# SENSOR_PB.net
KiCad netlist of a schematic drawn in Altium Designer
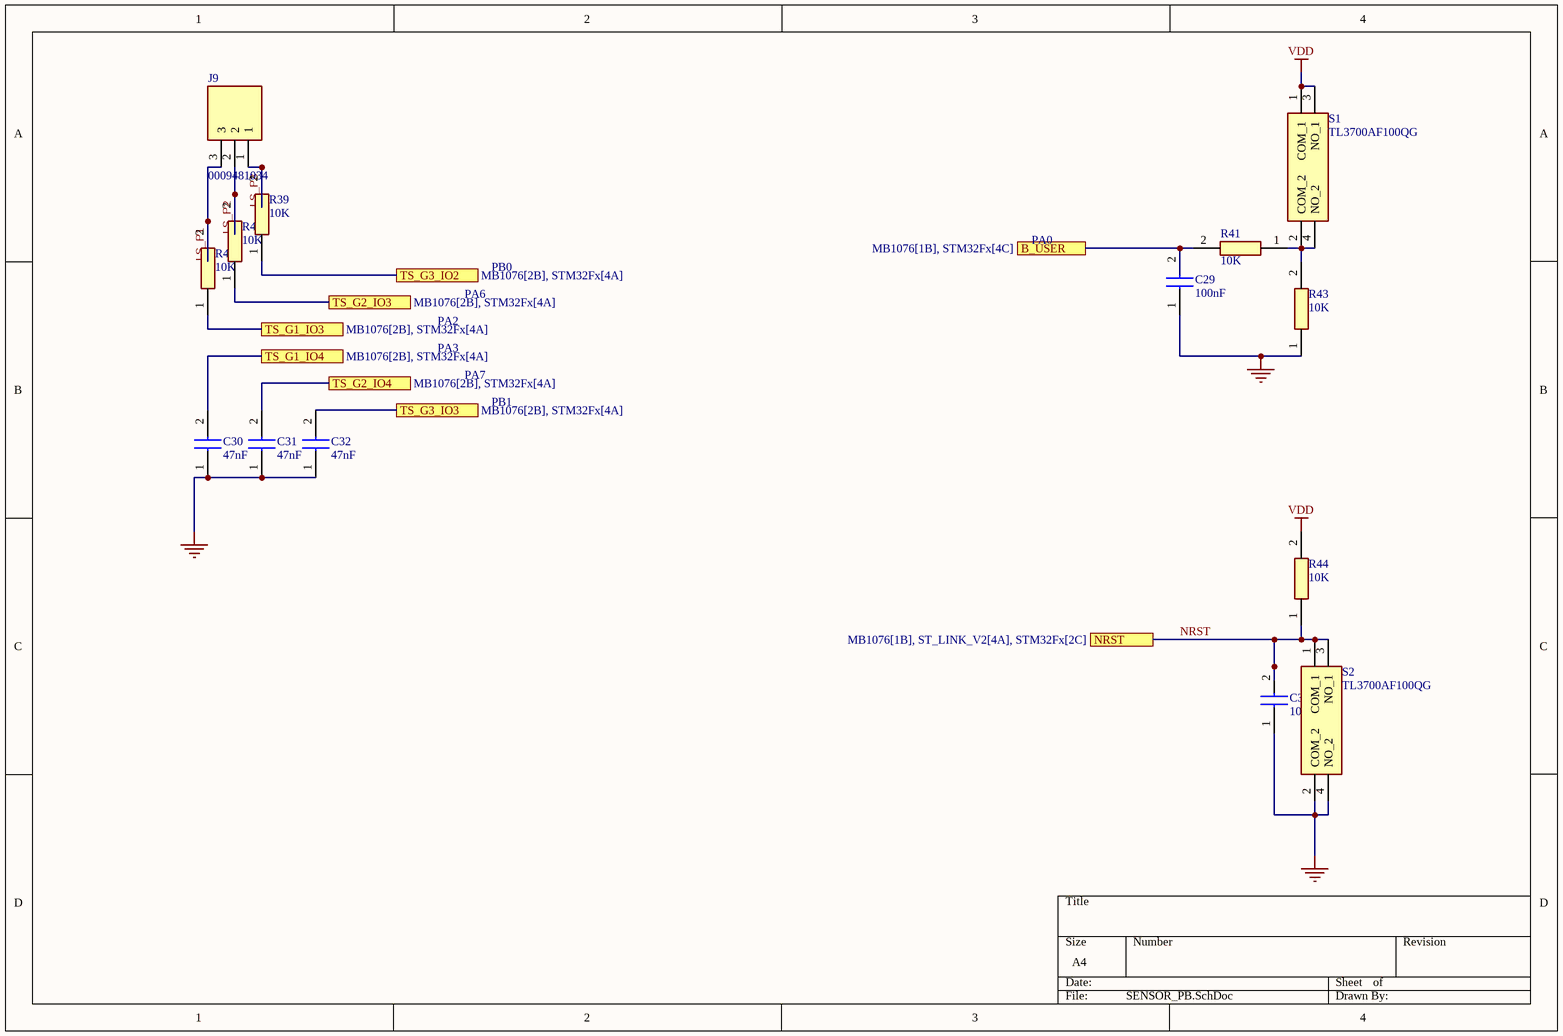
[diagram p0: SENSOR_PB.SchDoc]

(export (version "E")
  (design (tool "Eeschema 10.0.6"))
  (components
    (comp (ref "C29")
      (value "100nF")
      (footprint "SamacSys:ECHU_J1_J2_17_21")
      (description "Capacitor")
      (fields
        (field (name "MANUFACTURER_PART_NUMBER") "ECH-U1H102GX5")
        (field (name "MOUSER PART NUMBER") "667-ECH-U1H102GX5")
      )
      (libsource (lib "*") (part "ECH-U1H102GX5"))
    )
    (comp (ref "C30")
      (value "47nF")
      (footprint "SamacSys:ECHU_J1_J2_17_21")
      (description "Capacitor")
      (fields
        (field (name "MANUFACTURER_PART_NUMBER") "ECH-U1H102GX5")
        (field (name "MOUSER PART NUMBER") "667-ECH-U1H102GX5")
      )
      (libsource (lib "*") (part "ECH-U1H102GX5"))
    )
    (comp (ref "C31")
      (value "47nF")
      (footprint "SamacSys:ECHU_J1_J2_17_21")
      (description "Capacitor")
      (fields
        (field (name "MANUFACTURER_PART_NUMBER") "ECH-U1H102GX5")
        (field (name "MOUSER PART NUMBER") "667-ECH-U1H102GX5")
      )
      (libsource (lib "*") (part "ECH-U1H102GX5"))
    )
    (comp (ref "C32")
      (value "47nF")
      (footprint "SamacSys:ECHU_J1_J2_17_21")
      (description "Capacitor")
      (fields
        (field (name "MANUFACTURER_PART_NUMBER") "ECH-U1H102GX5")
        (field (name "MOUSER PART NUMBER") "667-ECH-U1H102GX5")
      )
      (libsource (lib "*") (part "ECH-U1H102GX5"))
    )
    (comp (ref "C33")
      (value "100nF")
      (footprint "SamacSys:ECHU_J1_J2_17_21")
      (description "Capacitor")
      (fields
        (field (name "MANUFACTURER_PART_NUMBER") "ECH-U1H102GX5")
        (field (name "MOUSER PART NUMBER") "667-ECH-U1H102GX5")
      )
      (libsource (lib "*") (part "ECH-U1H102GX5"))
    )
    (comp (ref "J9")
      (value "0009481034")
      (footprint "SamacSys:0009481034")
      (description "Connector")
      (libsource (lib "*") (part "0009481034"))
    )
    (comp (ref "R39")
      (value "10K")
      (footprint "SamacSys:RESC2012X60N")
      (description "Resistor")
      (fields (field (name "MANUFACTURER_PART_NUMBER") "RK73H2ATTD5111F"))
      (libsource (lib "") (part "RK73H2ATTD5111F_1"))
    )
    (comp (ref "R40")
      (value "10K")
      (footprint "SamacSys:RESC2012X60N")
      (description "Resistor")
      (fields (field (name "MANUFACTURER_PART_NUMBER") "RK73H2ATTD5111F"))
      (libsource (lib "") (part "RK73H2ATTD5111F_1"))
    )
    (comp (ref "R41")
      (value "10K")
      (footprint "SamacSys:RESC2012X60N")
      (description "Resistor")
      (fields (field (name "MANUFACTURER_PART_NUMBER") "RK73H2ATTD5111F"))
      (libsource (lib "*") (part "RK73H2ATTD5111F"))
    )
    (comp (ref "R42")
      (value "10K")
      (footprint "SamacSys:RESC2012X60N")
      (description "Resistor")
      (fields (field (name "MANUFACTURER_PART_NUMBER") "RK73H2ATTD5111F"))
      (libsource (lib "") (part "RK73H2ATTD5111F_1"))
    )
    (comp (ref "R43")
      (value "10K")
      (footprint "SamacSys:RESC2012X60N")
      (description "Resistor")
      (fields (field (name "MANUFACTURER_PART_NUMBER") "RK73H2ATTD5111F"))
      (libsource (lib "") (part "RK73H2ATTD5111F_1"))
    )
    (comp (ref "R44")
      (value "10K")
      (footprint "SamacSys:RESC2012X60N")
      (description "Resistor")
      (fields (field (name "MANUFACTURER_PART_NUMBER") "RK73H2ATTD5111F"))
      (libsource (lib "") (part "RK73H2ATTD5111F_1"))
    )
    (comp (ref "S1")
      (value "TL3700AF100QG")
      (footprint "SamacSys:TL3700AF100QG")
      (description "Switch")
      (fields (field (name "MOUSER PART NUMBER") "612-TL3700AF100QG"))
      (libsource (lib "*") (part "TL3700AF100QG"))
    )
    (comp (ref "S2")
      (value "TL3700AF100QG")
      (footprint "SamacSys:TL3700AF100QG")
      (description "Switch")
      (fields (field (name "MOUSER PART NUMBER") "612-TL3700AF100QG"))
      (libsource (lib "*") (part "TL3700AF100QG"))
    )
  )
  (nets
    (net (code "1") (name "/B_USER") (class "Default")
      (node (ref "C29") (pin "2") (pinfunction "2_2") (pintype "passive"))
      (node (ref "R41") (pin "2") (pinfunction "2_2") (pintype "passive"))
    )
    (net (code "2") (name "/LS_P1") (class "Default")
      (node (ref "J9") (pin "3") (pinfunction "3_3") (pintype "passive"))
      (node (ref "R42") (pin "2") (pinfunction "2_2") (pintype "passive"))
    )
    (net (code "3") (name "/LS_P2") (class "Default")
      (node (ref "J9") (pin "2") (pinfunction "2_2") (pintype "passive"))
      (node (ref "R40") (pin "2") (pinfunction "2_2") (pintype "passive"))
    )
    (net (code "4") (name "/LS_P3") (class "Default")
      (node (ref "J9") (pin "1") (pinfunction "1_1") (pintype "passive"))
      (node (ref "R39") (pin "2") (pinfunction "2_2") (pintype "passive"))
    )
    (net (code "5") (name "/NRST") (class "Default")
      (node (ref "C33") (pin "2") (pinfunction "2_2") (pintype "passive"))
      (node (ref "R44") (pin "1") (pinfunction "1_1") (pintype "passive"))
      (node (ref "S2") (pin "1") (pinfunction "COM_1_1") (pintype "passive"))
      (node (ref "S2") (pin "3") (pinfunction "NO_1_3") (pintype "passive"))
    )
    (net (code "6") (name "/TS_G1_IO3") (class "Default")
      (node (ref "R42") (pin "1") (pinfunction "1_1") (pintype "passive"))
    )
    (net (code "7") (name "/TS_G1_IO4") (class "Default")
      (node (ref "C30") (pin "2") (pinfunction "2_2") (pintype "passive"))
    )
    (net (code "8") (name "/TS_G2_IO3") (class "Default")
      (node (ref "R40") (pin "1") (pinfunction "1_1") (pintype "passive"))
    )
    (net (code "9") (name "/TS_G2_IO4") (class "Default")
      (node (ref "C31") (pin "2") (pinfunction "2_2") (pintype "passive"))
    )
    (net (code "10") (name "/TS_G3_IO2") (class "Default")
      (node (ref "R39") (pin "1") (pinfunction "1_1") (pintype "passive"))
    )
    (net (code "11") (name "/TS_G3_IO3") (class "Default")
      (node (ref "C32") (pin "2") (pinfunction "2_2") (pintype "passive"))
    )
    (net (code "12") (name "GND") (class "Default")
      (node (ref "C29") (pin "1") (pinfunction "1_1") (pintype "passive"))
      (node (ref "C30") (pin "1") (pinfunction "1_1") (pintype "passive"))
      (node (ref "C31") (pin "1") (pinfunction "1_1") (pintype "passive"))
      (node (ref "C32") (pin "1") (pinfunction "1_1") (pintype "passive"))
      (node (ref "C33") (pin "1") (pinfunction "1_1") (pintype "passive"))
      (node (ref "R43") (pin "1") (pinfunction "1_1") (pintype "passive"))
      (node (ref "S2") (pin "2") (pinfunction "COM_2_2") (pintype "passive"))
      (node (ref "S2") (pin "4") (pinfunction "NO_2_4") (pintype "passive"))
    )
    (net (code "13") (name "Net-(S1-COM_2)") (class "Default")
      (node (ref "R41") (pin "1") (pinfunction "1_1") (pintype "passive"))
      (node (ref "R43") (pin "2") (pinfunction "2_2") (pintype "passive"))
      (node (ref "S1") (pin "2") (pinfunction "COM_2_2") (pintype "passive"))
      (node (ref "S1") (pin "4") (pinfunction "NO_2_4") (pintype "passive"))
    )
    (net (code "14") (name "VDD") (class "Default")
      (node (ref "R44") (pin "2") (pinfunction "2_2") (pintype "passive"))
      (node (ref "S1") (pin "1") (pinfunction "COM_1_1") (pintype "passive"))
      (node (ref "S1") (pin "3") (pinfunction "NO_1_3") (pintype "passive"))
    )
  )
)
